# And_Or.net
KiCad netlist of a schematic drawn in EAGLE
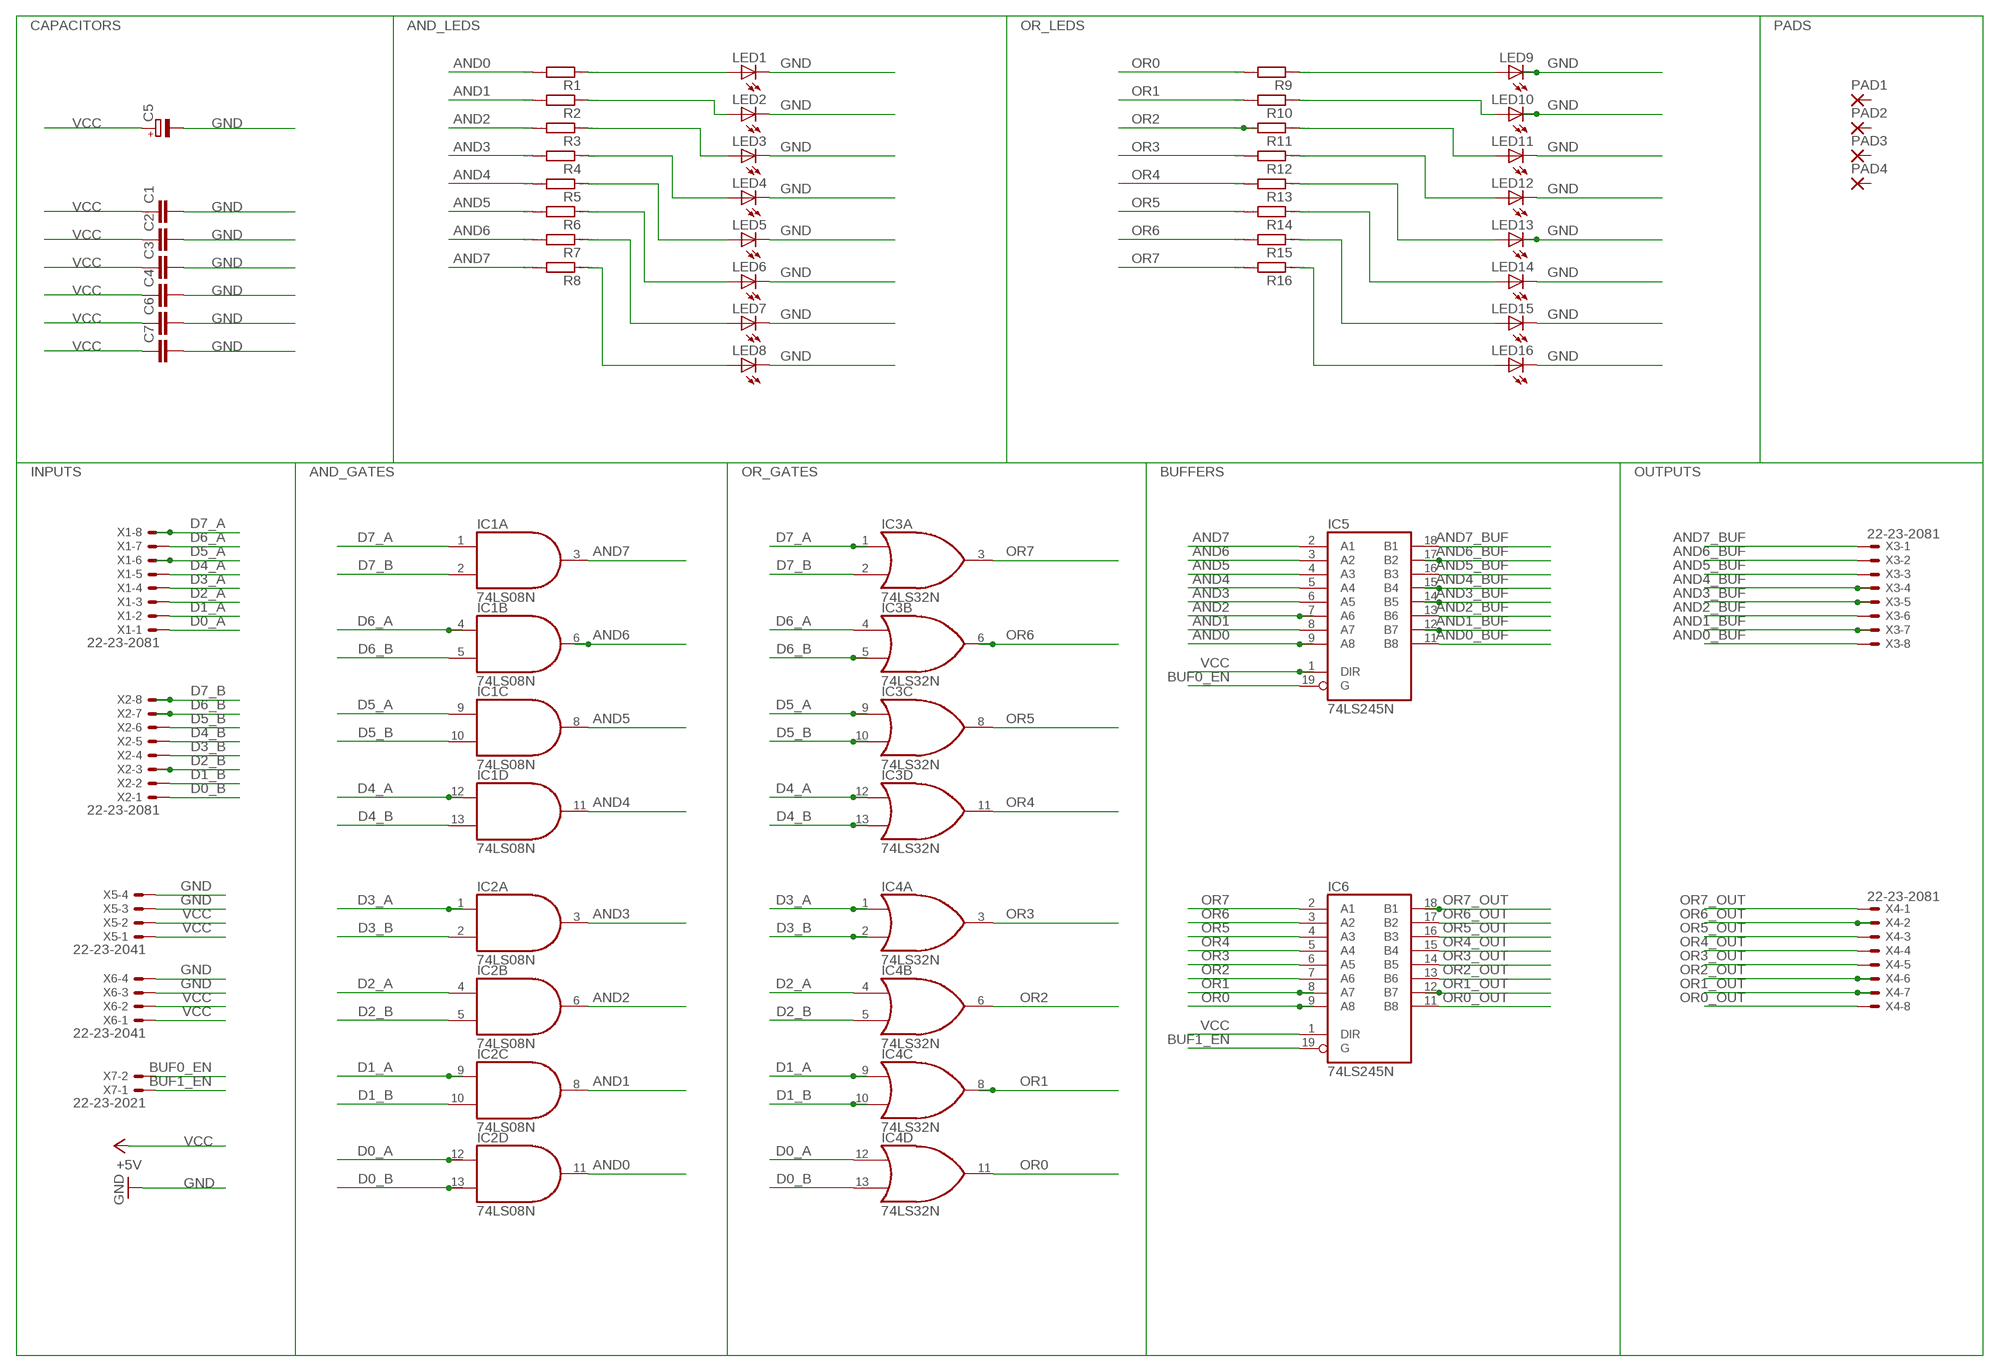
[diagram p0: schematic, sheet 1]

(export (version "E")
  (design (tool "Eeschema 10.0.6"))
  (components
    (comp (ref "C1")
      (value "C-EU025-025X050")
      (footprint "eagle-import:C025-025X050")
      (libsource (lib "eagle-import") (part "C-EU025-025X050"))
    )
    (comp (ref "C2")
      (value "C-EU025-025X050")
      (footprint "eagle-import:C025-025X050")
      (libsource (lib "eagle-import") (part "C-EU025-025X050"))
    )
    (comp (ref "C3")
      (value "C-EU025-025X050")
      (footprint "eagle-import:C025-025X050")
      (libsource (lib "eagle-import") (part "C-EU025-025X050"))
    )
    (comp (ref "C4")
      (value "C-EU025-025X050")
      (footprint "eagle-import:C025-025X050")
      (libsource (lib "eagle-import") (part "C-EU025-025X050"))
    )
    (comp (ref "C5")
      (value "CPOL-EUE2,5-6E")
      (footprint "eagle-import:E2,5-6E")
      (libsource (lib "eagle-import") (part "CPOL-EUE2,5-6E"))
    )
    (comp (ref "C6")
      (value "C-EU025-025X050")
      (footprint "eagle-import:C025-025X050")
      (libsource (lib "eagle-import") (part "C-EU025-025X050"))
    )
    (comp (ref "C7")
      (value "C-EU025-025X050")
      (footprint "eagle-import:C025-025X050")
      (libsource (lib "eagle-import") (part "C-EU025-025X050"))
    )
    (comp (ref "IC1")
      (value "74LS08N")
      (footprint "eagle-import:DIL14")
      (libsource (lib "eagle-import") (part "7408NLS"))
    )
    (comp (ref "IC2")
      (value "74LS08N")
      (footprint "eagle-import:DIL14")
      (libsource (lib "eagle-import") (part "7408NLS"))
    )
    (comp (ref "IC3")
      (value "74LS32N")
      (footprint "eagle-import:DIL14")
      (libsource (lib "eagle-import") (part "7432NLS"))
    )
    (comp (ref "IC4")
      (value "74LS32N")
      (footprint "eagle-import:DIL14")
      (libsource (lib "eagle-import") (part "7432NLS"))
    )
    (comp (ref "IC5")
      (value "74LS245N")
      (footprint "eagle-import:DIL20")
      (libsource (lib "eagle-import") (part "74245NLS"))
    )
    (comp (ref "IC6")
      (value "74LS245N")
      (footprint "eagle-import:DIL20")
      (libsource (lib "eagle-import") (part "74245NLS"))
    )
    (comp (ref "LED1")
      (value "LED5MM")
      (footprint "eagle-import:LED5MM")
      (libsource (lib "eagle-import") (part "LED5MM"))
    )
    (comp (ref "LED2")
      (value "LED5MM")
      (footprint "eagle-import:LED5MM")
      (libsource (lib "eagle-import") (part "LED5MM"))
    )
    (comp (ref "LED3")
      (value "LED5MM")
      (footprint "eagle-import:LED5MM")
      (libsource (lib "eagle-import") (part "LED5MM"))
    )
    (comp (ref "LED4")
      (value "LED5MM")
      (footprint "eagle-import:LED5MM")
      (libsource (lib "eagle-import") (part "LED5MM"))
    )
    (comp (ref "LED5")
      (value "LED5MM")
      (footprint "eagle-import:LED5MM")
      (libsource (lib "eagle-import") (part "LED5MM"))
    )
    (comp (ref "LED6")
      (value "LED5MM")
      (footprint "eagle-import:LED5MM")
      (libsource (lib "eagle-import") (part "LED5MM"))
    )
    (comp (ref "LED7")
      (value "LED5MM")
      (footprint "eagle-import:LED5MM")
      (libsource (lib "eagle-import") (part "LED5MM"))
    )
    (comp (ref "LED8")
      (value "LED5MM")
      (footprint "eagle-import:LED5MM")
      (libsource (lib "eagle-import") (part "LED5MM"))
    )
    (comp (ref "LED9")
      (value "LED5MM")
      (footprint "eagle-import:LED5MM")
      (libsource (lib "eagle-import") (part "LED5MM"))
    )
    (comp (ref "LED10")
      (value "LED5MM")
      (footprint "eagle-import:LED5MM")
      (libsource (lib "eagle-import") (part "LED5MM"))
    )
    (comp (ref "LED11")
      (value "LED5MM")
      (footprint "eagle-import:LED5MM")
      (libsource (lib "eagle-import") (part "LED5MM"))
    )
    (comp (ref "LED12")
      (value "LED5MM")
      (footprint "eagle-import:LED5MM")
      (libsource (lib "eagle-import") (part "LED5MM"))
    )
    (comp (ref "LED13")
      (value "LED5MM")
      (footprint "eagle-import:LED5MM")
      (libsource (lib "eagle-import") (part "LED5MM"))
    )
    (comp (ref "LED14")
      (value "LED5MM")
      (footprint "eagle-import:LED5MM")
      (libsource (lib "eagle-import") (part "LED5MM"))
    )
    (comp (ref "LED15")
      (value "LED5MM")
      (footprint "eagle-import:LED5MM")
      (libsource (lib "eagle-import") (part "LED5MM"))
    )
    (comp (ref "LED16")
      (value "LED5MM")
      (footprint "eagle-import:LED5MM")
      (libsource (lib "eagle-import") (part "LED5MM"))
    )
    (comp (ref "PAD1")
      (value "3,17/1,3")
      (footprint "eagle-import:3,17_1,3")
      (libsource (lib "eagle-import") (part "3,17/1,3"))
    )
    (comp (ref "PAD2")
      (value "3,17/1,3")
      (footprint "eagle-import:3,17_1,3")
      (libsource (lib "eagle-import") (part "3,17/1,3"))
    )
    (comp (ref "PAD3")
      (value "3,17/1,3")
      (footprint "eagle-import:3,17_1,3")
      (libsource (lib "eagle-import") (part "3,17/1,3"))
    )
    (comp (ref "PAD4")
      (value "3,17/1,3")
      (footprint "eagle-import:3,17_1,3")
      (libsource (lib "eagle-import") (part "3,17/1,3"))
    )
    (comp (ref "R1")
      (value "R0207/10")
      (footprint "eagle-import:0207_10")
      (libsource (lib "eagle-import") (part "R0207/10"))
    )
    (comp (ref "R2")
      (value "R0207/10")
      (footprint "eagle-import:0207_10")
      (libsource (lib "eagle-import") (part "R0207/10"))
    )
    (comp (ref "R3")
      (value "R0207/10")
      (footprint "eagle-import:0207_10")
      (libsource (lib "eagle-import") (part "R0207/10"))
    )
    (comp (ref "R4")
      (value "R0207/10")
      (footprint "eagle-import:0207_10")
      (libsource (lib "eagle-import") (part "R0207/10"))
    )
    (comp (ref "R5")
      (value "R0207/10")
      (footprint "eagle-import:0207_10")
      (libsource (lib "eagle-import") (part "R0207/10"))
    )
    (comp (ref "R6")
      (value "R0207/10")
      (footprint "eagle-import:0207_10")
      (libsource (lib "eagle-import") (part "R0207/10"))
    )
    (comp (ref "R7")
      (value "R0207/10")
      (footprint "eagle-import:0207_10")
      (libsource (lib "eagle-import") (part "R0207/10"))
    )
    (comp (ref "R8")
      (value "R0207/10")
      (footprint "eagle-import:0207_10")
      (libsource (lib "eagle-import") (part "R0207/10"))
    )
    (comp (ref "R9")
      (value "R0207/10")
      (footprint "eagle-import:0207_10")
      (libsource (lib "eagle-import") (part "R0207/10"))
    )
    (comp (ref "R10")
      (value "R0207/10")
      (footprint "eagle-import:0207_10")
      (libsource (lib "eagle-import") (part "R0207/10"))
    )
    (comp (ref "R11")
      (value "R0207/10")
      (footprint "eagle-import:0207_10")
      (libsource (lib "eagle-import") (part "R0207/10"))
    )
    (comp (ref "R12")
      (value "R0207/10")
      (footprint "eagle-import:0207_10")
      (libsource (lib "eagle-import") (part "R0207/10"))
    )
    (comp (ref "R13")
      (value "R0207/10")
      (footprint "eagle-import:0207_10")
      (libsource (lib "eagle-import") (part "R0207/10"))
    )
    (comp (ref "R14")
      (value "R0207/10")
      (footprint "eagle-import:0207_10")
      (libsource (lib "eagle-import") (part "R0207/10"))
    )
    (comp (ref "R15")
      (value "R0207/10")
      (footprint "eagle-import:0207_10")
      (libsource (lib "eagle-import") (part "R0207/10"))
    )
    (comp (ref "R16")
      (value "R0207/10")
      (footprint "eagle-import:0207_10")
      (libsource (lib "eagle-import") (part "R0207/10"))
    )
    (comp (ref "X1")
      (value "22-23-2081")
      (footprint "eagle-import:22-23-2081")
      (fields (field (name "MF") "MOLEX"))
      (libsource (lib "eagle-import") (part "22-23-2081"))
    )
    (comp (ref "X2")
      (value "22-23-2081")
      (footprint "eagle-import:22-23-2081")
      (fields (field (name "MF") "MOLEX"))
      (libsource (lib "eagle-import") (part "22-23-2081"))
    )
    (comp (ref "X3")
      (value "22-23-2081")
      (footprint "eagle-import:22-23-2081")
      (fields (field (name "MF") "MOLEX"))
      (libsource (lib "eagle-import") (part "22-23-2081"))
    )
    (comp (ref "X4")
      (value "22-23-2081")
      (footprint "eagle-import:22-23-2081")
      (fields (field (name "MF") "MOLEX"))
      (libsource (lib "eagle-import") (part "22-23-2081"))
    )
    (comp (ref "X5")
      (value "22-23-2041")
      (footprint "eagle-import:22-23-2041")
      (fields (field (name "MF") "MOLEX"))
      (libsource (lib "eagle-import") (part "22-23-2041"))
    )
    (comp (ref "X6")
      (value "22-23-2041")
      (footprint "eagle-import:22-23-2041")
      (fields (field (name "MF") "MOLEX"))
      (libsource (lib "eagle-import") (part "22-23-2041"))
    )
    (comp (ref "X7")
      (value "22-23-2021")
      (footprint "eagle-import:22-23-2021")
      (fields (field (name "MF") "MOLEX"))
      (libsource (lib "eagle-import") (part "22-23-2021"))
    )
  )
  (nets
    (net (code "1") (name "+5V") (class "Default")
      (node (ref "C1") (pin "1") (pinfunction "1_1") (pintype "passive"))
      (node (ref "C2") (pin "1") (pinfunction "1_1") (pintype "passive"))
      (node (ref "C3") (pin "1") (pinfunction "1_1") (pintype "passive"))
      (node (ref "C4") (pin "1") (pinfunction "1_1") (pintype "passive"))
      (node (ref "C5") (pin "+") (pinfunction "+_+") (pintype "passive"))
      (node (ref "C6") (pin "1") (pinfunction "1_1") (pintype "passive"))
      (node (ref "C7") (pin "1") (pinfunction "1_1") (pintype "passive"))
      (node (ref "IC5") (pin "1") (pinfunction "DIR_1") (pintype "input"))
      (node (ref "IC6") (pin "1") (pinfunction "DIR_1") (pintype "input"))
      (node (ref "X5") (pin "1") (pinfunction "S_1") (pintype "passive"))
      (node (ref "X5") (pin "2") (pinfunction "S_2") (pintype "passive"))
      (node (ref "X6") (pin "1") (pinfunction "S_1") (pintype "passive"))
      (node (ref "X6") (pin "2") (pinfunction "S_2") (pintype "passive"))
    )
    (net (code "2") (name "/AND0") (class "Default")
      (node (ref "IC2") (pin "11") (pinfunction "O_11") (pintype "output"))
      (node (ref "IC5") (pin "9") (pinfunction "A8_9") (pintype "bidirectional"))
      (node (ref "R1") (pin "2") (pinfunction "2_2") (pintype "passive"))
    )
    (net (code "3") (name "/AND0_BUF") (class "Default")
      (node (ref "IC5") (pin "11") (pinfunction "B8_11") (pintype "bidirectional"))
      (node (ref "X3") (pin "8") (pinfunction "S_8") (pintype "passive"))
    )
    (net (code "4") (name "/AND1") (class "Default")
      (node (ref "IC2") (pin "8") (pinfunction "O_8") (pintype "output"))
      (node (ref "IC5") (pin "8") (pinfunction "A7_8") (pintype "bidirectional"))
      (node (ref "R2") (pin "2") (pinfunction "2_2") (pintype "passive"))
    )
    (net (code "5") (name "/AND1_BUF") (class "Default")
      (node (ref "IC5") (pin "12") (pinfunction "B7_12") (pintype "bidirectional"))
      (node (ref "X3") (pin "7") (pinfunction "S_7") (pintype "passive"))
    )
    (net (code "6") (name "/AND2") (class "Default")
      (node (ref "IC2") (pin "6") (pinfunction "O_6") (pintype "output"))
      (node (ref "IC5") (pin "7") (pinfunction "A6_7") (pintype "bidirectional"))
      (node (ref "R3") (pin "2") (pinfunction "2_2") (pintype "passive"))
    )
    (net (code "7") (name "/AND2_BUF") (class "Default")
      (node (ref "IC5") (pin "13") (pinfunction "B6_13") (pintype "bidirectional"))
      (node (ref "X3") (pin "6") (pinfunction "S_6") (pintype "passive"))
    )
    (net (code "8") (name "/AND3") (class "Default")
      (node (ref "IC2") (pin "3") (pinfunction "O_3") (pintype "output"))
      (node (ref "IC5") (pin "6") (pinfunction "A5_6") (pintype "bidirectional"))
      (node (ref "R4") (pin "2") (pinfunction "2_2") (pintype "passive"))
    )
    (net (code "9") (name "/AND3_BUF") (class "Default")
      (node (ref "IC5") (pin "14") (pinfunction "B5_14") (pintype "bidirectional"))
      (node (ref "X3") (pin "5") (pinfunction "S_5") (pintype "passive"))
    )
    (net (code "10") (name "/AND4") (class "Default")
      (node (ref "IC1") (pin "11") (pinfunction "O_11") (pintype "output"))
      (node (ref "IC5") (pin "5") (pinfunction "A4_5") (pintype "bidirectional"))
      (node (ref "R5") (pin "2") (pinfunction "2_2") (pintype "passive"))
    )
    (net (code "11") (name "/AND4_BUF") (class "Default")
      (node (ref "IC5") (pin "15") (pinfunction "B4_15") (pintype "bidirectional"))
      (node (ref "X3") (pin "4") (pinfunction "S_4") (pintype "passive"))
    )
    (net (code "12") (name "/AND5") (class "Default")
      (node (ref "IC1") (pin "8") (pinfunction "O_8") (pintype "output"))
      (node (ref "IC5") (pin "4") (pinfunction "A3_4") (pintype "bidirectional"))
      (node (ref "R6") (pin "2") (pinfunction "2_2") (pintype "passive"))
    )
    (net (code "13") (name "/AND5_BUF") (class "Default")
      (node (ref "IC5") (pin "16") (pinfunction "B3_16") (pintype "bidirectional"))
      (node (ref "X3") (pin "3") (pinfunction "S_3") (pintype "passive"))
    )
    (net (code "14") (name "/AND6") (class "Default")
      (node (ref "IC1") (pin "6") (pinfunction "O_6") (pintype "output"))
      (node (ref "IC5") (pin "3") (pinfunction "A2_3") (pintype "bidirectional"))
      (node (ref "R7") (pin "2") (pinfunction "2_2") (pintype "passive"))
    )
    (net (code "15") (name "/AND6_BUF") (class "Default")
      (node (ref "IC5") (pin "17") (pinfunction "B2_17") (pintype "bidirectional"))
      (node (ref "X3") (pin "2") (pinfunction "S_2") (pintype "passive"))
    )
    (net (code "16") (name "/AND7") (class "Default")
      (node (ref "IC1") (pin "3") (pinfunction "O_3") (pintype "output"))
      (node (ref "IC5") (pin "2") (pinfunction "A1_2") (pintype "bidirectional"))
      (node (ref "R8") (pin "2") (pinfunction "2_2") (pintype "passive"))
    )
    (net (code "17") (name "/AND7_BUF") (class "Default")
      (node (ref "IC5") (pin "18") (pinfunction "B1_18") (pintype "bidirectional"))
      (node (ref "X3") (pin "1") (pinfunction "S_1") (pintype "passive"))
    )
    (net (code "18") (name "/BUF0_EN") (class "Default")
      (node (ref "IC5") (pin "19") (pinfunction "G_19") (pintype "input"))
      (node (ref "X7") (pin "2") (pinfunction "S_2") (pintype "passive"))
    )
    (net (code "19") (name "/BUF1_EN") (class "Default")
      (node (ref "IC6") (pin "19") (pinfunction "G_19") (pintype "input"))
      (node (ref "X7") (pin "1") (pinfunction "S_1") (pintype "passive"))
    )
    (net (code "20") (name "/D0_A") (class "Default")
      (node (ref "IC2") (pin "12") (pinfunction "I0_12") (pintype "input"))
      (node (ref "IC4") (pin "12") (pinfunction "I0_12") (pintype "input"))
      (node (ref "X1") (pin "1") (pinfunction "S_1") (pintype "passive"))
    )
    (net (code "21") (name "/D0_B") (class "Default")
      (node (ref "IC2") (pin "13") (pinfunction "I1_13") (pintype "input"))
      (node (ref "IC4") (pin "13") (pinfunction "I1_13") (pintype "input"))
      (node (ref "X2") (pin "1") (pinfunction "S_1") (pintype "passive"))
    )
    (net (code "22") (name "/D1_A") (class "Default")
      (node (ref "IC2") (pin "9") (pinfunction "I0_9") (pintype "input"))
      (node (ref "IC4") (pin "9") (pinfunction "I0_9") (pintype "input"))
      (node (ref "X1") (pin "2") (pinfunction "S_2") (pintype "passive"))
    )
    (net (code "23") (name "/D1_B") (class "Default")
      (node (ref "IC2") (pin "10") (pinfunction "I1_10") (pintype "input"))
      (node (ref "IC4") (pin "10") (pinfunction "I1_10") (pintype "input"))
      (node (ref "X2") (pin "2") (pinfunction "S_2") (pintype "passive"))
    )
    (net (code "24") (name "/D2_A") (class "Default")
      (node (ref "IC2") (pin "4") (pinfunction "I0_4") (pintype "input"))
      (node (ref "IC4") (pin "4") (pinfunction "I0_4") (pintype "input"))
      (node (ref "X1") (pin "3") (pinfunction "S_3") (pintype "passive"))
    )
    (net (code "25") (name "/D2_B") (class "Default")
      (node (ref "IC2") (pin "5") (pinfunction "I1_5") (pintype "input"))
      (node (ref "IC4") (pin "5") (pinfunction "I1_5") (pintype "input"))
      (node (ref "X2") (pin "3") (pinfunction "S_3") (pintype "passive"))
    )
    (net (code "26") (name "/D3_A") (class "Default")
      (node (ref "IC2") (pin "1") (pinfunction "I0_1") (pintype "input"))
      (node (ref "IC4") (pin "1") (pinfunction "I0_1") (pintype "input"))
      (node (ref "X1") (pin "4") (pinfunction "S_4") (pintype "passive"))
    )
    (net (code "27") (name "/D3_B") (class "Default")
      (node (ref "IC2") (pin "2") (pinfunction "I1_2") (pintype "input"))
      (node (ref "IC4") (pin "2") (pinfunction "I1_2") (pintype "input"))
      (node (ref "X2") (pin "4") (pinfunction "S_4") (pintype "passive"))
    )
    (net (code "28") (name "/D4_A") (class "Default")
      (node (ref "IC1") (pin "12") (pinfunction "I0_12") (pintype "input"))
      (node (ref "IC3") (pin "12") (pinfunction "I0_12") (pintype "input"))
      (node (ref "X1") (pin "5") (pinfunction "S_5") (pintype "passive"))
    )
    (net (code "29") (name "/D4_B") (class "Default")
      (node (ref "IC1") (pin "13") (pinfunction "I1_13") (pintype "input"))
      (node (ref "IC3") (pin "13") (pinfunction "I1_13") (pintype "input"))
      (node (ref "X2") (pin "5") (pinfunction "S_5") (pintype "passive"))
    )
    (net (code "30") (name "/D5_A") (class "Default")
      (node (ref "IC1") (pin "9") (pinfunction "I0_9") (pintype "input"))
      (node (ref "IC3") (pin "9") (pinfunction "I0_9") (pintype "input"))
      (node (ref "X1") (pin "6") (pinfunction "S_6") (pintype "passive"))
    )
    (net (code "31") (name "/D5_B") (class "Default")
      (node (ref "IC1") (pin "10") (pinfunction "I1_10") (pintype "input"))
      (node (ref "IC3") (pin "10") (pinfunction "I1_10") (pintype "input"))
      (node (ref "X2") (pin "6") (pinfunction "S_6") (pintype "passive"))
    )
    (net (code "32") (name "/D6_A") (class "Default")
      (node (ref "IC1") (pin "4") (pinfunction "I0_4") (pintype "input"))
      (node (ref "IC3") (pin "4") (pinfunction "I0_4") (pintype "input"))
      (node (ref "X1") (pin "7") (pinfunction "S_7") (pintype "passive"))
    )
    (net (code "33") (name "/D6_B") (class "Default")
      (node (ref "IC1") (pin "5") (pinfunction "I1_5") (pintype "input"))
      (node (ref "IC3") (pin "5") (pinfunction "I1_5") (pintype "input"))
      (node (ref "X2") (pin "7") (pinfunction "S_7") (pintype "passive"))
    )
    (net (code "34") (name "/D7_A") (class "Default")
      (node (ref "IC1") (pin "1") (pinfunction "I0_1") (pintype "input"))
      (node (ref "IC3") (pin "1") (pinfunction "I0_1") (pintype "input"))
      (node (ref "X1") (pin "8") (pinfunction "S_8") (pintype "passive"))
    )
    (net (code "35") (name "/D7_B") (class "Default")
      (node (ref "IC1") (pin "2") (pinfunction "I1_2") (pintype "input"))
      (node (ref "IC3") (pin "2") (pinfunction "I1_2") (pintype "input"))
      (node (ref "X2") (pin "8") (pinfunction "S_8") (pintype "passive"))
    )
    (net (code "36") (name "/OR0") (class "Default")
      (node (ref "IC4") (pin "11") (pinfunction "O_11") (pintype "output"))
      (node (ref "IC6") (pin "9") (pinfunction "A8_9") (pintype "bidirectional"))
      (node (ref "R9") (pin "2") (pinfunction "2_2") (pintype "passive"))
    )
    (net (code "37") (name "/OR0_OUT") (class "Default")
      (node (ref "IC6") (pin "11") (pinfunction "B8_11") (pintype "bidirectional"))
      (node (ref "X4") (pin "8") (pinfunction "S_8") (pintype "passive"))
    )
    (net (code "38") (name "/OR1") (class "Default")
      (node (ref "IC4") (pin "8") (pinfunction "O_8") (pintype "output"))
      (node (ref "IC6") (pin "8") (pinfunction "A7_8") (pintype "bidirectional"))
      (node (ref "R10") (pin "2") (pinfunction "2_2") (pintype "passive"))
    )
    (net (code "39") (name "/OR1_OUT") (class "Default")
      (node (ref "IC6") (pin "12") (pinfunction "B7_12") (pintype "bidirectional"))
      (node (ref "X4") (pin "7") (pinfunction "S_7") (pintype "passive"))
    )
    (net (code "40") (name "/OR2") (class "Default")
      (node (ref "IC4") (pin "6") (pinfunction "O_6") (pintype "output"))
      (node (ref "IC6") (pin "7") (pinfunction "A6_7") (pintype "bidirectional"))
      (node (ref "R11") (pin "2") (pinfunction "2_2") (pintype "passive"))
    )
    (net (code "41") (name "/OR2_OUT") (class "Default")
      (node (ref "IC6") (pin "13") (pinfunction "B6_13") (pintype "bidirectional"))
      (node (ref "X4") (pin "6") (pinfunction "S_6") (pintype "passive"))
    )
    (net (code "42") (name "/OR3") (class "Default")
      (node (ref "IC4") (pin "3") (pinfunction "O_3") (pintype "output"))
      (node (ref "IC6") (pin "6") (pinfunction "A5_6") (pintype "bidirectional"))
      (node (ref "R12") (pin "2") (pinfunction "2_2") (pintype "passive"))
    )
    (net (code "43") (name "/OR3_OUT") (class "Default")
      (node (ref "IC6") (pin "14") (pinfunction "B5_14") (pintype "bidirectional"))
      (node (ref "X4") (pin "5") (pinfunction "S_5") (pintype "passive"))
    )
    (net (code "44") (name "/OR4") (class "Default")
      (node (ref "IC3") (pin "11") (pinfunction "O_11") (pintype "output"))
      (node (ref "IC6") (pin "5") (pinfunction "A4_5") (pintype "bidirectional"))
      (node (ref "R13") (pin "2") (pinfunction "2_2") (pintype "passive"))
    )
    (net (code "45") (name "/OR4_OUT") (class "Default")
      (node (ref "IC6") (pin "15") (pinfunction "B4_15") (pintype "bidirectional"))
      (node (ref "X4") (pin "4") (pinfunction "S_4") (pintype "passive"))
    )
    (net (code "46") (name "/OR5") (class "Default")
      (node (ref "IC3") (pin "8") (pinfunction "O_8") (pintype "output"))
      (node (ref "IC6") (pin "4") (pinfunction "A3_4") (pintype "bidirectional"))
      (node (ref "R14") (pin "2") (pinfunction "2_2") (pintype "passive"))
    )
    (net (code "47") (name "/OR5_OUT") (class "Default")
      (node (ref "IC6") (pin "16") (pinfunction "B3_16") (pintype "bidirectional"))
      (node (ref "X4") (pin "3") (pinfunction "S_3") (pintype "passive"))
    )
    (net (code "48") (name "/OR6") (class "Default")
      (node (ref "IC3") (pin "6") (pinfunction "O_6") (pintype "output"))
      (node (ref "IC6") (pin "3") (pinfunction "A2_3") (pintype "bidirectional"))
      (node (ref "R15") (pin "2") (pinfunction "2_2") (pintype "passive"))
    )
    (net (code "49") (name "/OR6_OUT") (class "Default")
      (node (ref "IC6") (pin "17") (pinfunction "B2_17") (pintype "bidirectional"))
      (node (ref "X4") (pin "2") (pinfunction "S_2") (pintype "passive"))
    )
    (net (code "50") (name "/OR7") (class "Default")
      (node (ref "IC3") (pin "3") (pinfunction "O_3") (pintype "output"))
      (node (ref "IC6") (pin "2") (pinfunction "A1_2") (pintype "bidirectional"))
      (node (ref "R16") (pin "2") (pinfunction "2_2") (pintype "passive"))
    )
    (net (code "51") (name "/OR7_OUT") (class "Default")
      (node (ref "IC6") (pin "18") (pinfunction "B1_18") (pintype "bidirectional"))
      (node (ref "X4") (pin "1") (pinfunction "S_1") (pintype "passive"))
    )
    (net (code "52") (name "GND") (class "Default")
      (node (ref "C1") (pin "2") (pinfunction "2_2") (pintype "passive"))
      (node (ref "C2") (pin "2") (pinfunction "2_2") (pintype "passive"))
      (node (ref "C3") (pin "2") (pinfunction "2_2") (pintype "passive"))
      (node (ref "C4") (pin "2") (pinfunction "2_2") (pintype "passive"))
      (node (ref "C5") (pin "-") (pinfunction "-_-") (pintype "passive"))
      (node (ref "C6") (pin "2") (pinfunction "2_2") (pintype "passive"))
      (node (ref "C7") (pin "2") (pinfunction "2_2") (pintype "passive"))
      (node (ref "LED1") (pin "K") (pinfunction "C_K") (pintype "passive"))
      (node (ref "LED10") (pin "K") (pinfunction "C_K") (pintype "passive"))
      (node (ref "LED11") (pin "K") (pinfunction "C_K") (pintype "passive"))
      (node (ref "LED12") (pin "K") (pinfunction "C_K") (pintype "passive"))
      (node (ref "LED13") (pin "K") (pinfunction "C_K") (pintype "passive"))
      (node (ref "LED14") (pin "K") (pinfunction "C_K") (pintype "passive"))
      (node (ref "LED15") (pin "K") (pinfunction "C_K") (pintype "passive"))
      (node (ref "LED16") (pin "K") (pinfunction "C_K") (pintype "passive"))
      (node (ref "LED2") (pin "K") (pinfunction "C_K") (pintype "passive"))
      (node (ref "LED3") (pin "K") (pinfunction "C_K") (pintype "passive"))
      (node (ref "LED4") (pin "K") (pinfunction "C_K") (pintype "passive"))
      (node (ref "LED5") (pin "K") (pinfunction "C_K") (pintype "passive"))
      (node (ref "LED6") (pin "K") (pinfunction "C_K") (pintype "passive"))
      (node (ref "LED7") (pin "K") (pinfunction "C_K") (pintype "passive"))
      (node (ref "LED8") (pin "K") (pinfunction "C_K") (pintype "passive"))
      (node (ref "LED9") (pin "K") (pinfunction "C_K") (pintype "passive"))
      (node (ref "X5") (pin "3") (pinfunction "S_3") (pintype "passive"))
      (node (ref "X5") (pin "4") (pinfunction "S_4") (pintype "passive"))
      (node (ref "X6") (pin "3") (pinfunction "S_3") (pintype "passive"))
      (node (ref "X6") (pin "4") (pinfunction "S_4") (pintype "passive"))
    )
    (net (code "53") (name "Net-(LED1-PadA)") (class "Default")
      (node (ref "LED1") (pin "A") (pinfunction "A_A") (pintype "passive"))
      (node (ref "R1") (pin "1") (pinfunction "1_1") (pintype "passive"))
    )
    (net (code "54") (name "Net-(LED2-PadA)") (class "Default")
      (node (ref "LED2") (pin "A") (pinfunction "A_A") (pintype "passive"))
      (node (ref "R2") (pin "1") (pinfunction "1_1") (pintype "passive"))
    )
    (net (code "55") (name "Net-(LED3-PadA)") (class "Default")
      (node (ref "LED3") (pin "A") (pinfunction "A_A") (pintype "passive"))
      (node (ref "R3") (pin "1") (pinfunction "1_1") (pintype "passive"))
    )
    (net (code "56") (name "Net-(LED4-PadA)") (class "Default")
      (node (ref "LED4") (pin "A") (pinfunction "A_A") (pintype "passive"))
      (node (ref "R4") (pin "1") (pinfunction "1_1") (pintype "passive"))
    )
    (net (code "57") (name "Net-(LED5-PadA)") (class "Default")
      (node (ref "LED5") (pin "A") (pinfunction "A_A") (pintype "passive"))
      (node (ref "R5") (pin "1") (pinfunction "1_1") (pintype "passive"))
    )
    (net (code "58") (name "Net-(LED6-PadA)") (class "Default")
      (node (ref "LED6") (pin "A") (pinfunction "A_A") (pintype "passive"))
      (node (ref "R6") (pin "1") (pinfunction "1_1") (pintype "passive"))
    )
    (net (code "59") (name "Net-(LED7-PadA)") (class "Default")
      (node (ref "LED7") (pin "A") (pinfunction "A_A") (pintype "passive"))
      (node (ref "R7") (pin "1") (pinfunction "1_1") (pintype "passive"))
    )
    (net (code "60") (name "Net-(LED8-PadA)") (class "Default")
      (node (ref "LED8") (pin "A") (pinfunction "A_A") (pintype "passive"))
      (node (ref "R8") (pin "1") (pinfunction "1_1") (pintype "passive"))
    )
    (net (code "61") (name "Net-(LED9-PadA)") (class "Default")
      (node (ref "LED9") (pin "A") (pinfunction "A_A") (pintype "passive"))
      (node (ref "R9") (pin "1") (pinfunction "1_1") (pintype "passive"))
    )
    (net (code "62") (name "Net-(LED10-PadA)") (class "Default")
      (node (ref "LED10") (pin "A") (pinfunction "A_A") (pintype "passive"))
      (node (ref "R10") (pin "1") (pinfunction "1_1") (pintype "passive"))
    )
    (net (code "63") (name "Net-(LED11-PadA)") (class "Default")
      (node (ref "LED11") (pin "A") (pinfunction "A_A") (pintype "passive"))
      (node (ref "R11") (pin "1") (pinfunction "1_1") (pintype "passive"))
    )
    (net (code "64") (name "Net-(LED12-PadA)") (class "Default")
      (node (ref "LED12") (pin "A") (pinfunction "A_A") (pintype "passive"))
      (node (ref "R12") (pin "1") (pinfunction "1_1") (pintype "passive"))
    )
    (net (code "65") (name "Net-(LED13-PadA)") (class "Default")
      (node (ref "LED13") (pin "A") (pinfunction "A_A") (pintype "passive"))
      (node (ref "R13") (pin "1") (pinfunction "1_1") (pintype "passive"))
    )
    (net (code "66") (name "Net-(LED14-PadA)") (class "Default")
      (node (ref "LED14") (pin "A") (pinfunction "A_A") (pintype "passive"))
      (node (ref "R14") (pin "1") (pinfunction "1_1") (pintype "passive"))
    )
    (net (code "67") (name "Net-(LED15-PadA)") (class "Default")
      (node (ref "LED15") (pin "A") (pinfunction "A_A") (pintype "passive"))
      (node (ref "R15") (pin "1") (pinfunction "1_1") (pintype "passive"))
    )
    (net (code "68") (name "Net-(LED16-PadA)") (class "Default")
      (node (ref "LED16") (pin "A") (pinfunction "A_A") (pintype "passive"))
      (node (ref "R16") (pin "1") (pinfunction "1_1") (pintype "passive"))
    )
    (net (code "69") (name "unconnected-(PAD1-P-Pad1)") (class "Default")
      (node (ref "PAD1") (pin "1") (pinfunction "P_1") (pintype "passive"))
    )
    (net (code "70") (name "unconnected-(PAD2-P-Pad1)") (class "Default")
      (node (ref "PAD2") (pin "1") (pinfunction "P_1") (pintype "passive"))
    )
    (net (code "71") (name "unconnected-(PAD3-P-Pad1)") (class "Default")
      (node (ref "PAD3") (pin "1") (pinfunction "P_1") (pintype "passive"))
    )
    (net (code "72") (name "unconnected-(PAD4-P-Pad1)") (class "Default")
      (node (ref "PAD4") (pin "1") (pinfunction "P_1") (pintype "passive"))
    )
  )
)
